# 1bitMux2.net
KiCad netlist of a schematic drawn in Altium Designer
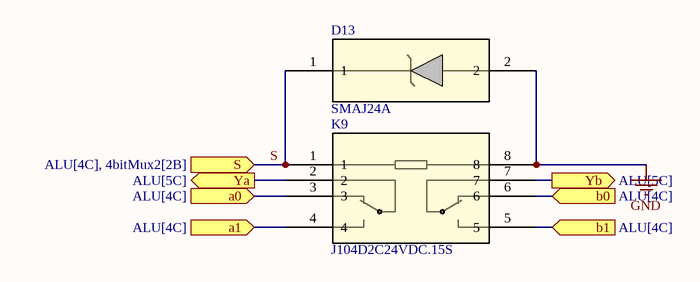
[diagram p0: 1bitMux2.SchDoc]

(export (version "E")
  (design (tool "Eeschema 10.0.6"))
  (components
    (comp (ref "D13")
      (value "SMAJ24A")
      (footprint "DI SMAJ24A")
      (description "SMAJ Series 400 W 24 V Uni-Directional Surface Mount TVS Diode - DO-214AC")
      (fields (field (name "MANUFACTURER") "Littelfuse"))
      (libsource (lib "Schlib1") (part "DI SMAJ24A"))
    )
    (comp (ref "K9")
      (value "J104D2C24VDC.15S")
      (footprint "Relay J104D2C24VDC.15S")
      (description "Relay Ul Gen Purp DPDT 2C 24VDC")
      (fields (field (name "MANUFACTURER") "CIT Relay & Switch"))
      (libsource (lib "Schlib1") (part "Relay J104D2C24VDC.15S"))
    )
  )
  (nets
    (net (code "1") (name "/S") (class "Default")
      (node (ref "D13") (pin "1") (pinfunction "1_1") (pintype "passive"))
      (node (ref "K9") (pin "1") (pinfunction "1_1") (pintype "passive"))
    )
    (net (code "2") (name "/Ya") (class "Default")
      (node (ref "K9") (pin "2") (pinfunction "2_2") (pintype "passive"))
    )
    (net (code "3") (name "/Yb") (class "Default")
      (node (ref "K9") (pin "7") (pinfunction "7_7") (pintype "passive"))
    )
    (net (code "4") (name "/a0") (class "Default")
      (node (ref "K9") (pin "3") (pinfunction "3_3") (pintype "passive"))
    )
    (net (code "5") (name "/a1") (class "Default")
      (node (ref "K9") (pin "4") (pinfunction "4_4") (pintype "passive"))
    )
    (net (code "6") (name "/b0") (class "Default")
      (node (ref "K9") (pin "6") (pinfunction "6_6") (pintype "passive"))
    )
    (net (code "7") (name "/b1") (class "Default")
      (node (ref "K9") (pin "5") (pinfunction "5_5") (pintype "passive"))
    )
    (net (code "8") (name "GND") (class "Default")
      (node (ref "D13") (pin "2") (pinfunction "2_2") (pintype "passive"))
      (node (ref "K9") (pin "8") (pinfunction "8_8") (pintype "passive"))
    )
  )
)
